# Marcelo-v1.net
KiCad netlist of a schematic drawn in Altium Designer
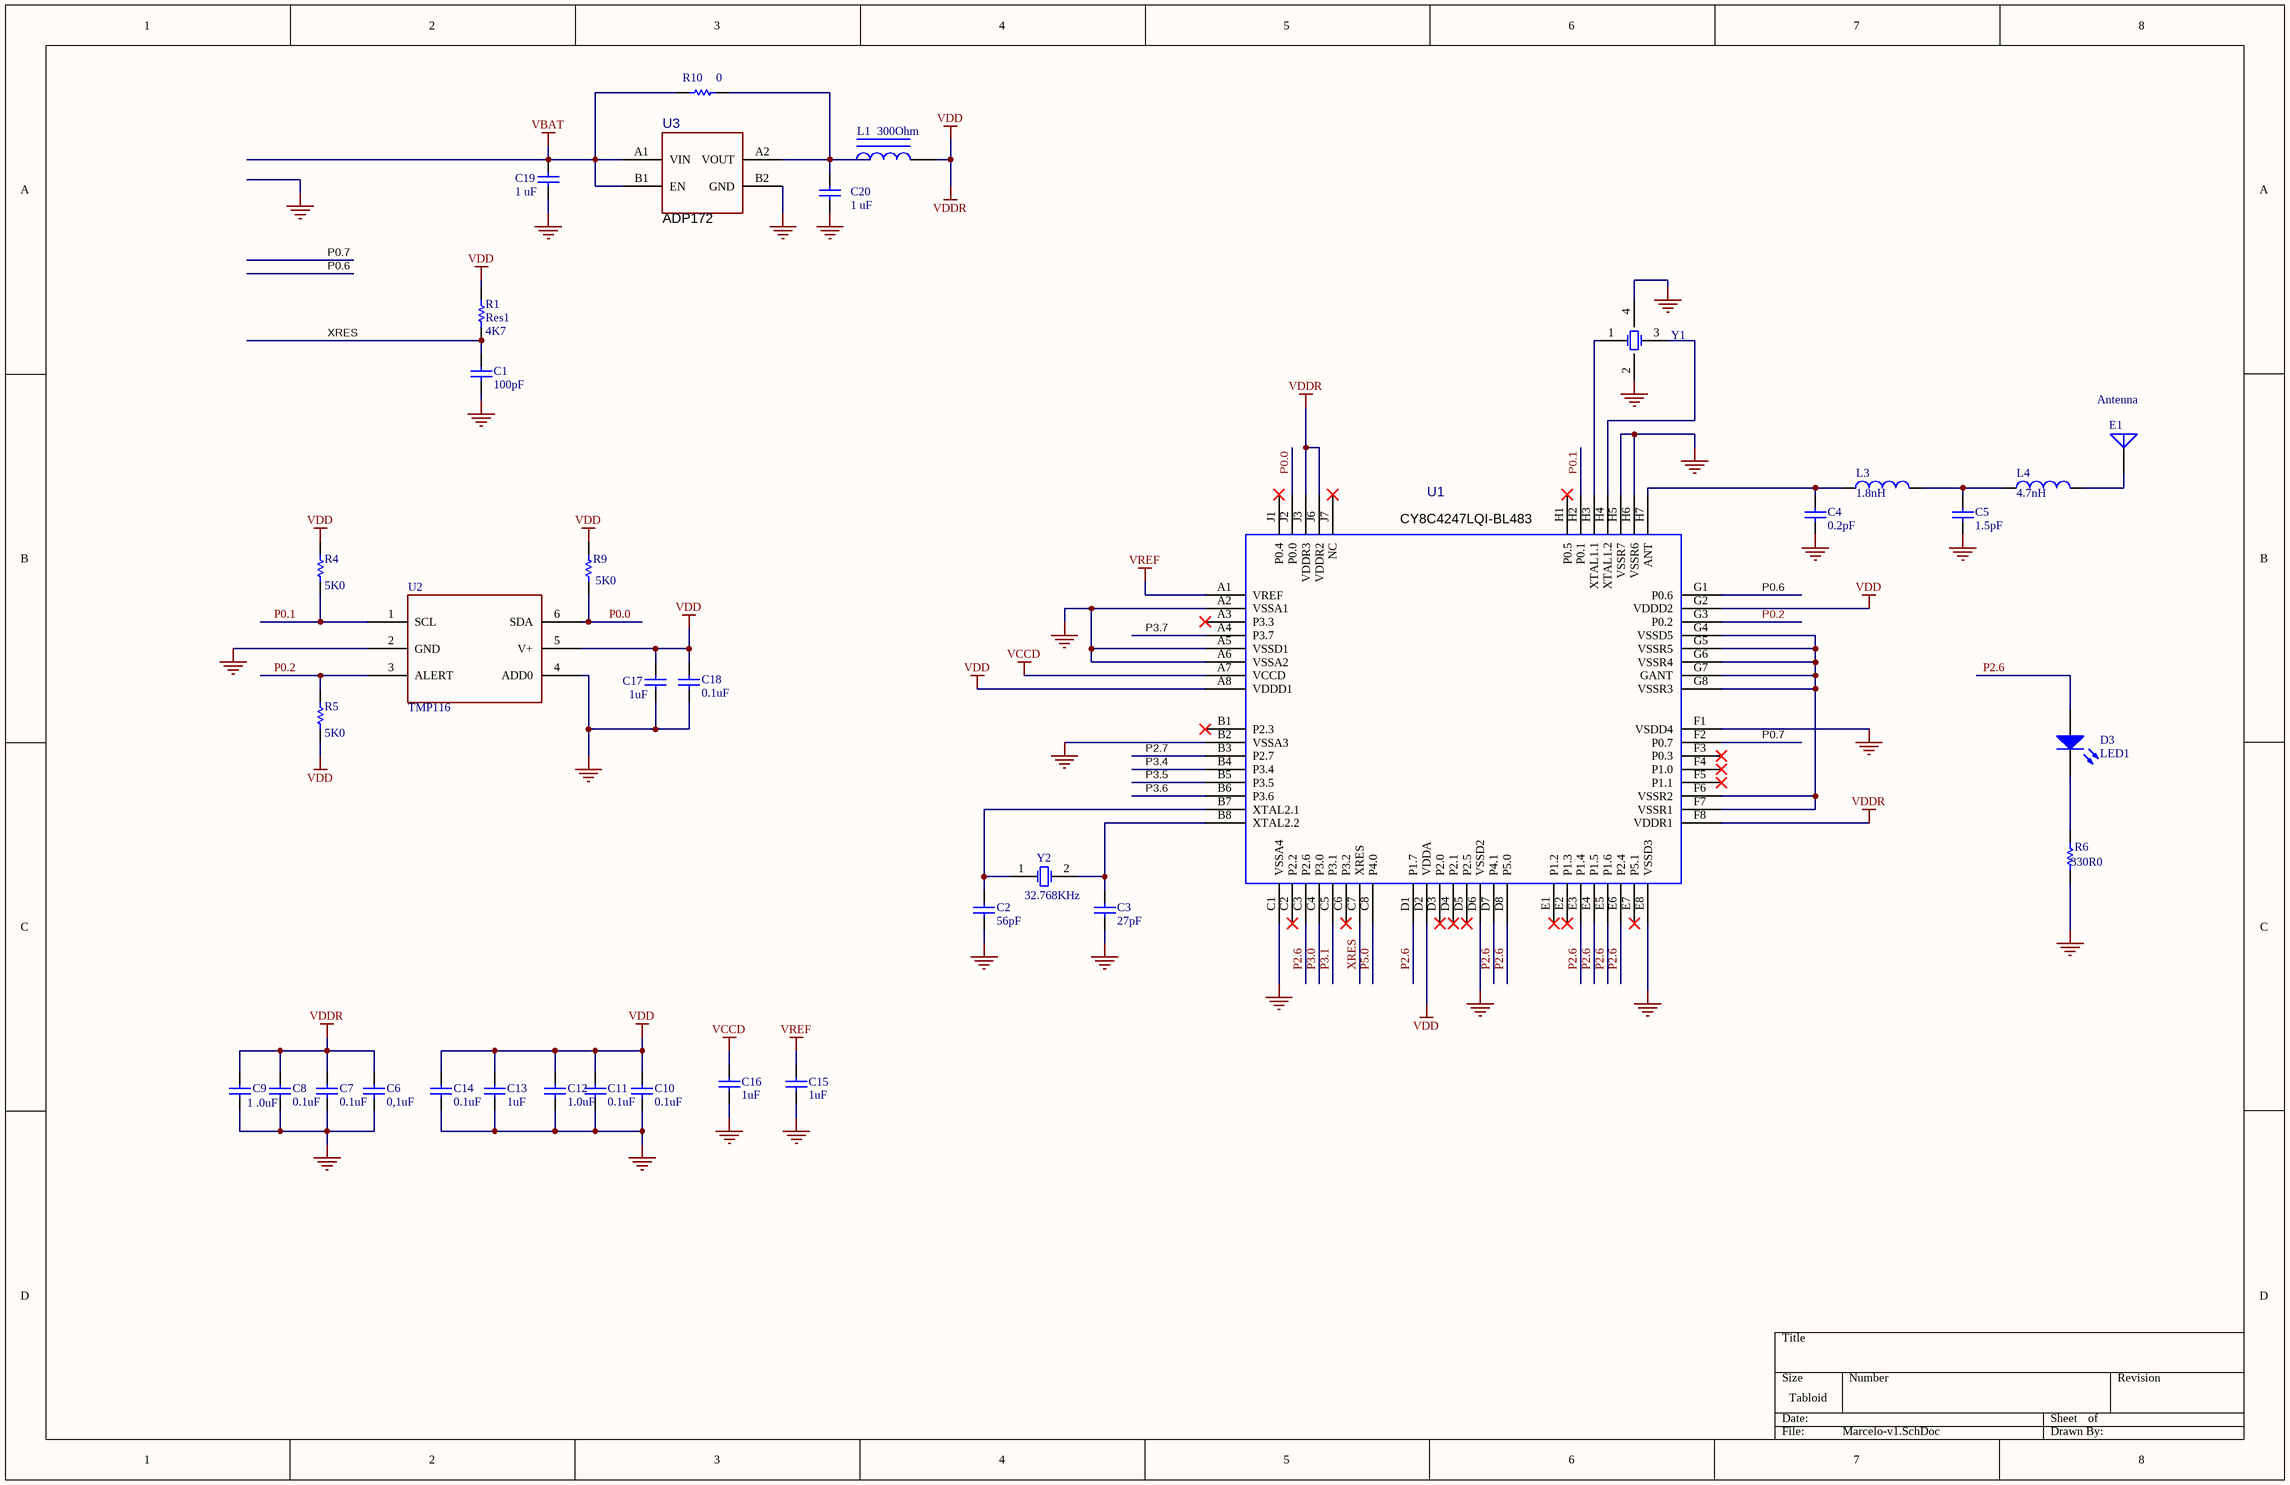
[diagram p0: Marcelo-v1.SchDoc]

(export (version "E")
  (design (tool "Eeschema 10.0.6"))
  (components
    (comp (ref "C1")
      (value "100pF")
      (footprint "0201")
      (description "Capacitor")
      (fields (field (name "PUBLISHER") "Altium Limited"))
      (libsource (lib "Miscellaneous Devices") (part "Cap"))
    )
    (comp (ref "C2")
      (value "56pF")
      (footprint "0201")
      (description "Capacitor")
      (fields (field (name "PUBLISHER") "Altium Limited"))
      (libsource (lib "Miscellaneous Devices") (part "Cap"))
    )
    (comp (ref "C3")
      (value "27pF")
      (footprint "0201")
      (description "Capacitor")
      (fields (field (name "PUBLISHER") "Altium Limited"))
      (libsource (lib "Miscellaneous Devices") (part "Cap"))
    )
    (comp (ref "C4")
      (value "0.2pF")
      (footprint "0201")
      (description "Capacitor")
      (fields (field (name "PUBLISHER") "Altium Limited"))
      (libsource (lib "Miscellaneous Devices") (part "Cap"))
    )
    (comp (ref "C5")
      (value "1.5pF")
      (footprint "0201")
      (description "Capacitor")
      (fields (field (name "PUBLISHER") "Altium Limited"))
      (libsource (lib "Miscellaneous Devices") (part "Cap"))
    )
    (comp (ref "C6")
      (value "0,1uF")
      (footprint "0201")
      (description "Capacitor")
      (fields (field (name "PUBLISHER") "Altium Limited"))
      (libsource (lib "Miscellaneous Devices") (part "Cap"))
    )
    (comp (ref "C7")
      (value "0.1uF")
      (footprint "0201")
      (description "Capacitor")
      (fields (field (name "PUBLISHER") "Altium Limited"))
      (libsource (lib "Miscellaneous Devices") (part "Cap"))
    )
    (comp (ref "C8")
      (value "0.1uF")
      (footprint "0201")
      (description "Capacitor")
      (fields (field (name "PUBLISHER") "Altium Limited"))
      (libsource (lib "Miscellaneous Devices") (part "Cap"))
    )
    (comp (ref "C9")
      (value "1 .0uF")
      (footprint "0201")
      (description "Capacitor")
      (fields (field (name "PUBLISHER") "Altium Limited"))
      (libsource (lib "Miscellaneous Devices") (part "Cap"))
    )
    (comp (ref "C10")
      (value "0.1uF")
      (footprint "0201")
      (description "Capacitor")
      (fields (field (name "PUBLISHER") "Altium Limited"))
      (libsource (lib "Miscellaneous Devices") (part "Cap"))
    )
    (comp (ref "C11")
      (value "0.1uF")
      (footprint "0201")
      (description "Capacitor")
      (fields (field (name "PUBLISHER") "Altium Limited"))
      (libsource (lib "Miscellaneous Devices") (part "Cap"))
    )
    (comp (ref "C12")
      (value "1.0uF")
      (footprint "0201")
      (description "Capacitor")
      (fields (field (name "PUBLISHER") "Altium Limited"))
      (libsource (lib "Miscellaneous Devices") (part "Cap"))
    )
    (comp (ref "C13")
      (value "1uF")
      (footprint "0201")
      (description "Capacitor")
      (fields (field (name "PUBLISHER") "Altium Limited"))
      (libsource (lib "Miscellaneous Devices") (part "Cap"))
    )
    (comp (ref "C14")
      (value "0.1uF")
      (footprint "0201")
      (description "Capacitor")
      (fields (field (name "PUBLISHER") "Altium Limited"))
      (libsource (lib "Miscellaneous Devices") (part "Cap"))
    )
    (comp (ref "C15")
      (value "1uF")
      (footprint "0201")
      (description "Capacitor")
      (fields (field (name "PUBLISHER") "Altium Limited"))
      (libsource (lib "Miscellaneous Devices") (part "Cap"))
    )
    (comp (ref "C16")
      (value "1uF")
      (footprint "0201")
      (description "Capacitor")
      (fields (field (name "PUBLISHER") "Altium Limited"))
      (libsource (lib "Miscellaneous Devices") (part "Cap"))
    )
    (comp (ref "C17")
      (value "1uF")
      (footprint "0201")
      (description "Capacitor")
      (fields (field (name "PUBLISHER") "Altium Limited"))
      (libsource (lib "Miscellaneous Devices") (part "Cap"))
    )
    (comp (ref "C18")
      (value "0.1uF")
      (footprint "0201")
      (description "Capacitor")
      (fields (field (name "PUBLISHER") "Altium Limited"))
      (libsource (lib "Miscellaneous Devices") (part "Cap"))
    )
    (comp (ref "C19")
      (value "1 uF")
      (footprint "0201")
      (description "Capacitor 1608-1155-1-ND X7R 1812")
      (fields (field (name "PUBLISHER") "Altium Limited"))
      (libsource (lib "Miscellaneous Devices") (part "Cap"))
    )
    (comp (ref "C20")
      (value "1 uF")
      (footprint "0201")
      (description "Capacitor 1608-1155-1-ND X7R 1812")
      (fields (field (name "PUBLISHER") "Altium Limited"))
      (libsource (lib "Miscellaneous Devices") (part "Cap"))
    )
    (comp (ref "D3")
      (value "LED1")
      (footprint "0402")
      (description "Typical RED GaAs LED")
      (fields (field (name "PUBLISHER") "Altium Limited"))
      (libsource (lib "Miscellaneous Devices") (part "LED1"))
    )
    (comp (ref "E1")
      (value "Antenna")
      (footprint "ANTENA-YSK")
      (description "Generic Antenna")
      (fields (field (name "PUBLISHER") "Altium Limited"))
      (libsource (lib "Miscellaneous Devices") (part "Antenna"))
    )
    (comp (ref "L1")
      (value "300Ohm")
      (footprint "0201")
      (description "Magnetic-Core Inductor")
      (fields (field (name "Comment") "Inductor Iron") (field (name "PUBLISHER") "Altium Limited"))
      (libsource (lib "Miscellaneous Devices") (part "Inductor Iron"))
    )
    (comp (ref "L3")
      (value "1.8nH")
      (footprint "0201")
      (fields (field (name "PUBLISHER") "Altium Limited"))
      (libsource (lib "Miscellaneous Devices") (part "Inductor"))
    )
    (comp (ref "L4")
      (value "4.7nH")
      (footprint "0201")
      (description "Inductor")
      (fields (field (name "PUBLISHER") "Altium Limited"))
      (libsource (lib "Miscellaneous Devices") (part "Inductor"))
    )
    (comp (ref "R1")
      (value "Res1")
      (footprint "0201")
      (description "Resistor")
      (fields (field (name "ALTIUM_VALUE") "4K7") (field (name "PUBLISHER") "Altium Limited"))
      (libsource (lib "Miscellaneous Devices") (part "Res1"))
    )
    (comp (ref "R4")
      (value "5K0")
      (footprint "0201")
      (description "Resistor")
      (fields (field (name "Comment") "Res1") (field (name "PUBLISHER") "Altium Limited"))
      (libsource (lib "Miscellaneous Devices") (part "Res1"))
    )
    (comp (ref "R5")
      (value "5K0")
      (footprint "0201")
      (description "Resistor")
      (fields (field (name "Comment") "Res1") (field (name "PUBLISHER") "Altium Limited"))
      (libsource (lib "Miscellaneous Devices") (part "Res1"))
    )
    (comp (ref "R6")
      (value "330R0")
      (footprint "0201")
      (description "Resistor")
      (fields (field (name "Comment") "Res1") (field (name "PUBLISHER") "Altium Limited"))
      (libsource (lib "Miscellaneous Devices") (part "Res1"))
    )
    (comp (ref "R9")
      (value "5K0")
      (footprint "0201")
      (description "Resistor")
      (fields (field (name "Comment") "Res1") (field (name "PUBLISHER") "Altium Limited"))
      (libsource (lib "Miscellaneous Devices") (part "Res1"))
    )
    (comp (ref "R10")
      (value "0")
      (footprint "0201")
      (description "Resistor")
      (fields (field (name "Comment") "Res1") (field (name "PUBLISHER") "Altium Limited"))
      (libsource (lib "Miscellaneous Devices") (part "Res1"))
    )
    (comp (ref "U1")
      (value "CY8C4247LQI-BL483")
      (footprint "WLCSP-68")
      (libsource (lib "DESA") (part "CYBL10X6X"))
    )
    (comp (ref "U2") (value "TMP116") (libsource (lib "TAR0410-1") (part "TMP116")))
    (comp (ref "U3") (value "ADP172") (footprint "ADP172") (libsource (lib "GyroV3") (part "ADP172")))
    (comp (ref "Y1") (value "FA-20H") (footprint "FA-20H") (libsource (lib "YSK") (part "FA-20H")))
    (comp (ref "Y2")
      (value "32.768KHz")
      (footprint "ABS05")
      (description "Crystal Oscillator")
      (fields (field (name "PUBLISHER") "Altium Limited"))
      (libsource (lib "Miscellaneous Devices") (part "XTAL"))
    )
  )
  (nets
    (net (code "1") (name "/P0.0") (class "Default")
      (node (ref "R9") (pin "1") (pinfunction "1_1") (pintype "passive"))
      (node (ref "U1") (pin "J2") (pinfunction "P0.0_J2") (pintype "passive"))
      (node (ref "U2") (pin "6") (pinfunction "SDA_6") (pintype "passive"))
    )
    (net (code "2") (name "/P0.1") (class "Default")
      (node (ref "R4") (pin "1") (pinfunction "1_1") (pintype "passive"))
      (node (ref "U1") (pin "H2") (pinfunction "P0.1_H2") (pintype "passive"))
      (node (ref "U2") (pin "1") (pinfunction "SCL_1") (pintype "passive"))
    )
    (net (code "3") (name "/P0.2") (class "Default")
      (node (ref "R5") (pin "2") (pinfunction "2_2") (pintype "passive"))
      (node (ref "U1") (pin "G3") (pinfunction "P0.2_G3") (pintype "passive"))
      (node (ref "U2") (pin "3") (pinfunction "ALERT_3") (pintype "passive"))
    )
    (net (code "4") (name "/P0.6") (class "Default")
      (node (ref "U1") (pin "G1") (pinfunction "P0.6_G1") (pintype "passive"))
    )
    (net (code "5") (name "/P0.7") (class "Default")
      (node (ref "U1") (pin "F2") (pinfunction "P0.7_F2") (pintype "passive"))
    )
    (net (code "6") (name "/P2.6") (class "Default")
      (node (ref "D3") (pin "1") (pinfunction "A_1") (pintype "passive"))
      (node (ref "U1") (pin "C3") (pinfunction "P2.6_C3") (pintype "passive"))
      (node (ref "U1") (pin "D1") (pinfunction "P1.7_D1") (pintype "passive"))
      (node (ref "U1") (pin "D7") (pinfunction "P4.1_D7") (pintype "passive"))
      (node (ref "U1") (pin "D8") (pinfunction "P5.0_D8") (pintype "passive"))
      (node (ref "U1") (pin "E3") (pinfunction "P1.4_E3") (pintype "passive"))
      (node (ref "U1") (pin "E4") (pinfunction "P1.5_E4") (pintype "passive"))
      (node (ref "U1") (pin "E5") (pinfunction "P1.6_E5") (pintype "passive"))
      (node (ref "U1") (pin "E6") (pinfunction "P2.4_E6") (pintype "passive"))
    )
    (net (code "7") (name "/P2.7") (class "Default")
      (node (ref "U1") (pin "B3") (pinfunction "P2.7_B3") (pintype "passive"))
    )
    (net (code "8") (name "/P3.0") (class "Default")
      (node (ref "U1") (pin "C4") (pinfunction "P3.0_C4") (pintype "passive"))
    )
    (net (code "9") (name "/P3.1") (class "Default")
      (node (ref "U1") (pin "C5") (pinfunction "P3.1_C5") (pintype "passive"))
    )
    (net (code "10") (name "/P3.4") (class "Default")
      (node (ref "U1") (pin "B4") (pinfunction "P3.4_B4") (pintype "passive"))
    )
    (net (code "11") (name "/P3.5") (class "Default")
      (node (ref "U1") (pin "B5") (pinfunction "P3.5_B5") (pintype "passive"))
    )
    (net (code "12") (name "/P3.6") (class "Default")
      (node (ref "U1") (pin "B6") (pinfunction "P3.6_B6") (pintype "passive"))
    )
    (net (code "13") (name "/P3.7") (class "Default")
      (node (ref "U1") (pin "A4") (pinfunction "P3.7_A4") (pintype "passive"))
    )
    (net (code "14") (name "/P5.0") (class "Default")
      (node (ref "U1") (pin "C8") (pinfunction "P4.0_C8") (pintype "passive"))
    )
    (net (code "15") (name "/XRES") (class "Default")
      (node (ref "C1") (pin "1") (pinfunction "1_1") (pintype "passive"))
      (node (ref "R1") (pin "1") (pinfunction "1_1") (pintype "passive"))
      (node (ref "U1") (pin "C7") (pinfunction "XRES_C7") (pintype "passive"))
    )
    (net (code "16") (name "GND") (class "Default")
      (node (ref "C1") (pin "2") (pinfunction "2_2") (pintype "passive"))
      (node (ref "C10") (pin "2") (pinfunction "2_2") (pintype "passive"))
      (node (ref "C11") (pin "2") (pinfunction "2_2") (pintype "passive"))
      (node (ref "C12") (pin "2") (pinfunction "2_2") (pintype "passive"))
      (node (ref "C13") (pin "2") (pinfunction "2_2") (pintype "passive"))
      (node (ref "C14") (pin "2") (pinfunction "2_2") (pintype "passive"))
      (node (ref "C15") (pin "2") (pinfunction "2_2") (pintype "passive"))
      (node (ref "C16") (pin "2") (pinfunction "2_2") (pintype "passive"))
      (node (ref "C17") (pin "1") (pinfunction "1_1") (pintype "passive"))
      (node (ref "C18") (pin "1") (pinfunction "1_1") (pintype "passive"))
      (node (ref "C19") (pin "1") (pinfunction "1_1") (pintype "passive"))
      (node (ref "C2") (pin "2") (pinfunction "2_2") (pintype "passive"))
      (node (ref "C20") (pin "1") (pinfunction "1_1") (pintype "passive"))
      (node (ref "C3") (pin "2") (pinfunction "2_2") (pintype "passive"))
      (node (ref "C4") (pin "2") (pinfunction "2_2") (pintype "passive"))
      (node (ref "C5") (pin "2") (pinfunction "2_2") (pintype "passive"))
      (node (ref "C6") (pin "2") (pinfunction "2_2") (pintype "passive"))
      (node (ref "C7") (pin "2") (pinfunction "2_2") (pintype "passive"))
      (node (ref "C8") (pin "2") (pinfunction "2_2") (pintype "passive"))
      (node (ref "C9") (pin "2") (pinfunction "2_2") (pintype "passive"))
      (node (ref "R6") (pin "1") (pinfunction "1_1") (pintype "passive"))
      (node (ref "U1") (pin "A2") (pinfunction "VSSA1_A2") (pintype "passive"))
      (node (ref "U1") (pin "A5") (pinfunction "VSSD1_A5") (pintype "passive"))
      (node (ref "U1") (pin "A6") (pinfunction "VSSA2_A6") (pintype "passive"))
      (node (ref "U1") (pin "B2") (pinfunction "VSSA3_B2") (pintype "passive"))
      (node (ref "U1") (pin "C1") (pinfunction "VSSA4_C1") (pintype "passive"))
      (node (ref "U1") (pin "D6") (pinfunction "VSSD2_D6") (pintype "passive"))
      (node (ref "U1") (pin "E8") (pinfunction "VSSD3_E8") (pintype "passive"))
      (node (ref "U1") (pin "F1") (pinfunction "VSDD4_F1") (pintype "passive"))
      (node (ref "U1") (pin "H5") (pinfunction "VSSR7_H5") (pintype "passive"))
      (node (ref "U1") (pin "H6") (pinfunction "VSSR6_H6") (pintype "passive"))
      (node (ref "U2") (pin "2") (pinfunction "GND_2") (pintype "passive"))
      (node (ref "U2") (pin "4") (pinfunction "ADD0_4") (pintype "passive"))
      (node (ref "U3") (pin "B2") (pinfunction "GND_B2") (pintype "passive"))
      (node (ref "Y1") (pin "2") (pinfunction "GND_2") (pintype "passive"))
      (node (ref "Y1") (pin "4") (pinfunction "GND_4") (pintype "passive"))
    )
    (net (code "17") (name "Net-(C5-Pad1)") (class "Default")
      (node (ref "C5") (pin "1") (pinfunction "1_1") (pintype "passive"))
      (node (ref "L3") (pin "2") (pinfunction "2_2") (pintype "passive"))
      (node (ref "L4") (pin "1") (pinfunction "1_1") (pintype "passive"))
    )
    (net (code "18") (name "Net-(D3-K)") (class "Default")
      (node (ref "D3") (pin "2") (pinfunction "K_2") (pintype "passive"))
      (node (ref "R6") (pin "2") (pinfunction "2_2") (pintype "passive"))
    )
    (net (code "19") (name "Net-(E1-A)") (class "Default")
      (node (ref "E1") (pin "1") (pinfunction "A_1") (pintype "passive"))
      (node (ref "L4") (pin "2") (pinfunction "2_2") (pintype "passive"))
    )
    (net (code "20") (name "Net-(U1-ANT)") (class "Default")
      (node (ref "C4") (pin "1") (pinfunction "1_1") (pintype "passive"))
      (node (ref "L3") (pin "1") (pinfunction "1_1") (pintype "passive"))
      (node (ref "U1") (pin "H7") (pinfunction "ANT_H7") (pintype "passive"))
    )
    (net (code "21") (name "Net-(U1-GANT)") (class "Default")
      (node (ref "U1") (pin "F6") (pinfunction "VSSR2_F6") (pintype "passive"))
      (node (ref "U1") (pin "F7") (pinfunction "VSSR1_F7") (pintype "passive"))
      (node (ref "U1") (pin "G4") (pinfunction "VSSD5_G4") (pintype "passive"))
      (node (ref "U1") (pin "G5") (pinfunction "VSSR5_G5") (pintype "passive"))
      (node (ref "U1") (pin "G6") (pinfunction "VSSR4_G6") (pintype "passive"))
      (node (ref "U1") (pin "G7") (pinfunction "GANT_G7") (pintype "passive"))
      (node (ref "U1") (pin "G8") (pinfunction "VSSR3_G8") (pintype "passive"))
    )
    (net (code "22") (name "Net-(U1-XTAL1.1)") (class "Default")
      (node (ref "U1") (pin "H3") (pinfunction "XTAL1.1_H3") (pintype "passive"))
      (node (ref "Y1") (pin "1") (pinfunction "OSC1_1") (pintype "passive"))
    )
    (net (code "23") (name "Net-(U1-XTAL1.2)") (class "Default")
      (node (ref "U1") (pin "H4") (pinfunction "XTAL1.2_H4") (pintype "passive"))
      (node (ref "Y1") (pin "3") (pinfunction "OSC2_3") (pintype "passive"))
    )
    (net (code "24") (name "Net-(U1-XTAL2.1)") (class "Default")
      (node (ref "C2") (pin "1") (pinfunction "1_1") (pintype "passive"))
      (node (ref "U1") (pin "B7") (pinfunction "XTAL2.1_B7") (pintype "passive"))
      (node (ref "Y2") (pin "1") (pinfunction "OSC1_1") (pintype "passive"))
    )
    (net (code "25") (name "Net-(U1-XTAL2.2)") (class "Default")
      (node (ref "C3") (pin "1") (pinfunction "1_1") (pintype "passive"))
      (node (ref "U1") (pin "B8") (pinfunction "XTAL2.2_B8") (pintype "passive"))
      (node (ref "Y2") (pin "2") (pinfunction "OSC2_2") (pintype "passive"))
    )
    (net (code "26") (name "Net-(U3-VOUT)") (class "Default")
      (node (ref "C20") (pin "2") (pinfunction "2_2") (pintype "passive"))
      (node (ref "L1") (pin "1") (pinfunction "1_1") (pintype "passive"))
      (node (ref "R10") (pin "1") (pinfunction "1_1") (pintype "passive"))
      (node (ref "U3") (pin "A2") (pinfunction "VOUT_A2") (pintype "passive"))
    )
    (net (code "27") (name "VBAT") (class "Default")
      (node (ref "C19") (pin "2") (pinfunction "2_2") (pintype "passive"))
      (node (ref "R10") (pin "2") (pinfunction "2_2") (pintype "passive"))
      (node (ref "U3") (pin "A1") (pinfunction "VIN_A1") (pintype "passive"))
      (node (ref "U3") (pin "B1") (pinfunction "EN_B1") (pintype "passive"))
    )
    (net (code "28") (name "VCCD") (class "Default")
      (node (ref "C16") (pin "1") (pinfunction "1_1") (pintype "passive"))
      (node (ref "U1") (pin "A7") (pinfunction "VCCD_A7") (pintype "passive"))
    )
    (net (code "29") (name "VDD") (class "Default")
      (node (ref "C10") (pin "1") (pinfunction "1_1") (pintype "passive"))
      (node (ref "C11") (pin "1") (pinfunction "1_1") (pintype "passive"))
      (node (ref "C12") (pin "1") (pinfunction "1_1") (pintype "passive"))
      (node (ref "C13") (pin "1") (pinfunction "1_1") (pintype "passive"))
      (node (ref "C14") (pin "1") (pinfunction "1_1") (pintype "passive"))
      (node (ref "C17") (pin "2") (pinfunction "2_2") (pintype "passive"))
      (node (ref "C18") (pin "2") (pinfunction "2_2") (pintype "passive"))
      (node (ref "C6") (pin "1") (pinfunction "1_1") (pintype "passive"))
      (node (ref "C7") (pin "1") (pinfunction "1_1") (pintype "passive"))
      (node (ref "C8") (pin "1") (pinfunction "1_1") (pintype "passive"))
      (node (ref "C9") (pin "1") (pinfunction "1_1") (pintype "passive"))
      (node (ref "L1") (pin "2") (pinfunction "2_2") (pintype "passive"))
      (node (ref "R1") (pin "2") (pinfunction "2_2") (pintype "passive"))
      (node (ref "R4") (pin "2") (pinfunction "2_2") (pintype "passive"))
      (node (ref "R5") (pin "1") (pinfunction "1_1") (pintype "passive"))
      (node (ref "R9") (pin "2") (pinfunction "2_2") (pintype "passive"))
      (node (ref "U1") (pin "A8") (pinfunction "VDDD1_A8") (pintype "passive"))
      (node (ref "U1") (pin "D2") (pinfunction "VDDA_D2") (pintype "passive"))
      (node (ref "U1") (pin "F8") (pinfunction "VDDR1_F8") (pintype "passive"))
      (node (ref "U1") (pin "G2") (pinfunction "VDDD2_G2") (pintype "passive"))
      (node (ref "U1") (pin "J3") (pinfunction "VDDR3_J3") (pintype "passive"))
      (node (ref "U1") (pin "J6") (pinfunction "VDDR2_J6") (pintype "passive"))
      (node (ref "U2") (pin "5") (pinfunction "V+_5") (pintype "passive"))
    )
    (net (code "30") (name "VREF") (class "Default")
      (node (ref "C15") (pin "1") (pinfunction "1_1") (pintype "passive"))
      (node (ref "U1") (pin "A1") (pinfunction "VREF_A1") (pintype "passive"))
    )
    (net (code "31") (name "unconnected-(U1-NC-PadJ7)") (class "Default")
      (node (ref "U1") (pin "J7") (pinfunction "NC_J7") (pintype "passive+no_connect"))
    )
    (net (code "32") (name "unconnected-(U1-P0.3-PadF3)") (class "Default")
      (node (ref "U1") (pin "F3") (pinfunction "P0.3_F3") (pintype "passive+no_connect"))
    )
    (net (code "33") (name "unconnected-(U1-P0.4-PadJ1)") (class "Default")
      (node (ref "U1") (pin "J1") (pinfunction "P0.4_J1") (pintype "passive+no_connect"))
    )
    (net (code "34") (name "unconnected-(U1-P0.5-PadH1)") (class "Default")
      (node (ref "U1") (pin "H1") (pinfunction "P0.5_H1") (pintype "passive+no_connect"))
    )
    (net (code "35") (name "unconnected-(U1-P1.0-PadF4)") (class "Default")
      (node (ref "U1") (pin "F4") (pinfunction "P1.0_F4") (pintype "passive+no_connect"))
    )
    (net (code "36") (name "unconnected-(U1-P1.1-PadF5)") (class "Default")
      (node (ref "U1") (pin "F5") (pinfunction "P1.1_F5") (pintype "passive+no_connect"))
    )
    (net (code "37") (name "unconnected-(U1-P1.2-PadE1)") (class "Default")
      (node (ref "U1") (pin "E1") (pinfunction "P1.2_E1") (pintype "passive+no_connect"))
    )
    (net (code "38") (name "unconnected-(U1-P1.3-PadE2)") (class "Default")
      (node (ref "U1") (pin "E2") (pinfunction "P1.3_E2") (pintype "passive+no_connect"))
    )
    (net (code "39") (name "unconnected-(U1-P2.0-PadD3)") (class "Default")
      (node (ref "U1") (pin "D3") (pinfunction "P2.0_D3") (pintype "passive+no_connect"))
    )
    (net (code "40") (name "unconnected-(U1-P2.1-PadD4)") (class "Default")
      (node (ref "U1") (pin "D4") (pinfunction "P2.1_D4") (pintype "passive+no_connect"))
    )
    (net (code "41") (name "unconnected-(U1-P2.2-PadC2)") (class "Default")
      (node (ref "U1") (pin "C2") (pinfunction "P2.2_C2") (pintype "passive+no_connect"))
    )
    (net (code "42") (name "unconnected-(U1-P2.3-PadB1)") (class "Default")
      (node (ref "U1") (pin "B1") (pinfunction "P2.3_B1") (pintype "passive+no_connect"))
    )
    (net (code "43") (name "unconnected-(U1-P2.5-PadD5)") (class "Default")
      (node (ref "U1") (pin "D5") (pinfunction "P2.5_D5") (pintype "passive+no_connect"))
    )
    (net (code "44") (name "unconnected-(U1-P3.2-PadC6)") (class "Default")
      (node (ref "U1") (pin "C6") (pinfunction "P3.2_C6") (pintype "passive+no_connect"))
    )
    (net (code "45") (name "unconnected-(U1-P3.3-PadA3)") (class "Default")
      (node (ref "U1") (pin "A3") (pinfunction "P3.3_A3") (pintype "passive+no_connect"))
    )
    (net (code "46") (name "unconnected-(U1-P5.1-PadE7)") (class "Default")
      (node (ref "U1") (pin "E7") (pinfunction "P5.1_E7") (pintype "passive+no_connect"))
    )
  )
)
